# power-v3v8.net
KiCad netlist of a schematic drawn in Altium Designer
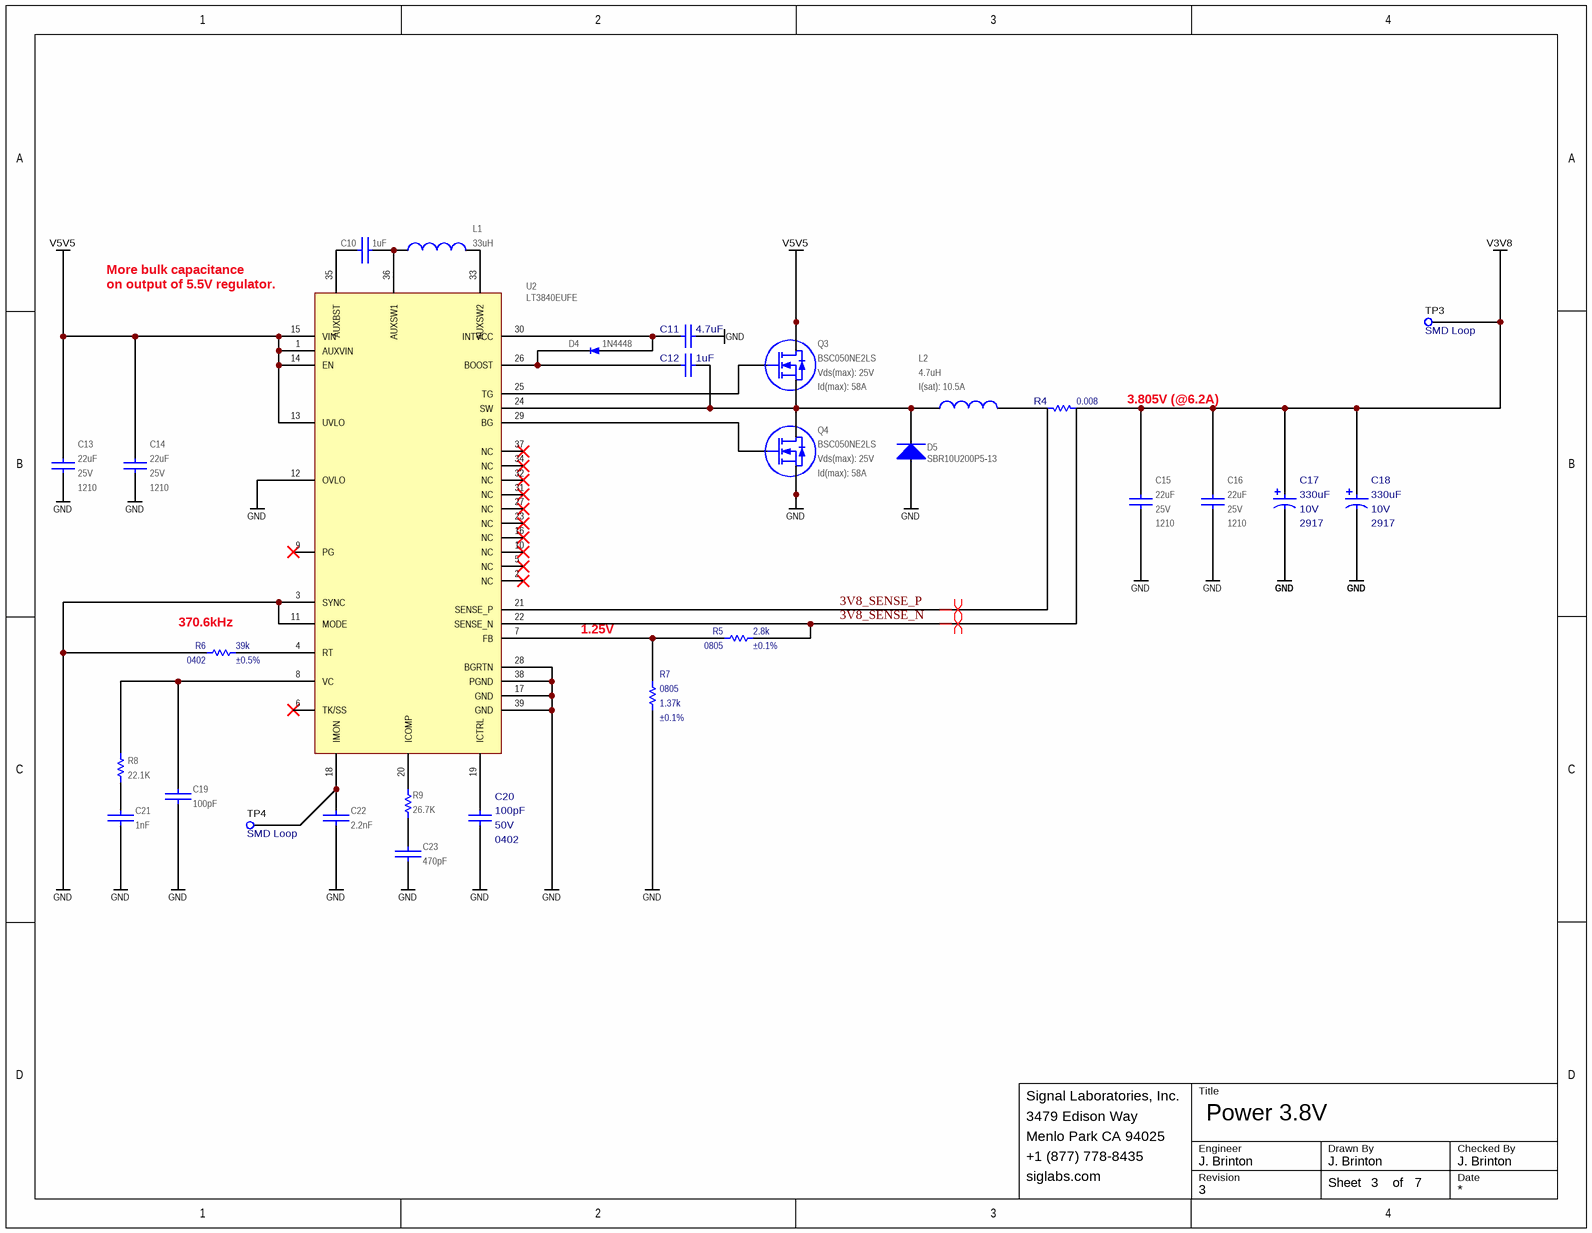
[diagram p0: power-v3v8.SchDoc]

(export (version "E")
  (design (tool "Eeschema 10.0.6"))
  (components
    (comp (ref "C10")
      (value "1uF")
      (footprint "CAPC100X50X55L25N")
      (description "Ceramic Capacitor 1uF ±10% 10V X5R 0402")
      (fields (field (name "MANUFACTURER") "Murata") (field (name "TOLERANCE") "±10%"))
      (libsource (lib "*") (part "CAP"))
    )
    (comp (ref "C11")
      (value "4.7uF")
      (footprint "CAPC160X80X90L20NA")
      (description "Ceramic Capacitor 4.7uF ±10% 25V X5R 0603")
      (fields (field (name "MANUFACTURER") "Samsung") (field (name "TOLERANCE") "±10%"))
      (libsource (lib "capacitors") (part "CAP"))
    )
    (comp (ref "C12")
      (value "1uF")
      (footprint "CAPC100X50X55L25N")
      (description "Ceramic Capacitor 1uF ±10% 10V X5R 0402")
      (fields (field (name "MANUFACTURER") "Murata") (field (name "TOLERANCE") "±10%"))
      (libsource (lib "capacitors") (part "CAP"))
    )
    (comp (ref "C13")
      (value "22uF")
      (footprint "CAPC320X250X270L50N")
      (description "Ceramic Capacitor 22uF ±10% 25V X7R 1210")
      (fields
        (field (name "MANUFACTURER") "Murata")
        (field (name "TOLERANCE") "±10%")
        (field (name "VOLTAGE") "25V")
        (field (name "PACKAGE") "1210")
      )
      (libsource (lib "generic") (part "CAP"))
    )
    (comp (ref "C14")
      (value "22uF")
      (footprint "CAPC320X250X270L50N")
      (description "Ceramic Capacitor 22uF ±10% 25V X7R 1210")
      (fields
        (field (name "MANUFACTURER") "Murata")
        (field (name "TOLERANCE") "±10%")
        (field (name "VOLTAGE") "25V")
        (field (name "PACKAGE") "1210")
      )
      (libsource (lib "generic") (part "CAP"))
    )
    (comp (ref "C15")
      (value "22uF")
      (footprint "CAPC320X250X270L50N")
      (description "Ceramic Capacitor 22uF ±10% 25V X7R 1210")
      (fields
        (field (name "MANUFACTURER") "Murata")
        (field (name "TOLERANCE") "±10%")
        (field (name "VOLTAGE") "25V")
        (field (name "PACKAGE") "1210")
      )
      (libsource (lib "generic") (part "CAP"))
    )
    (comp (ref "C16")
      (value "22uF")
      (footprint "CAPC320X250X270L50N")
      (description "Ceramic Capacitor 22uF ±10% 25V X7R 1210")
      (fields
        (field (name "MANUFACTURER") "Murata")
        (field (name "TOLERANCE") "±10%")
        (field (name "VOLTAGE") "25V")
        (field (name "PACKAGE") "1210")
      )
      (libsource (lib "generic") (part "CAP"))
    )
    (comp (ref "C17")
      (value "330uF")
      (footprint "CAPPM730X435X310L135X240N")
      (description "Tantalum Capacitor 330uF ±10% 10V 2917")
      (fields
        (field (name "MANUFACTURER") "AVX")
        (field (name "TOLERANCE") "±10%")
        (field (name "PACKAGE") "2917")
        (field (name "VOLTAGE") "10V")
      )
      (libsource (lib "avx") (part "CAP_POL"))
    )
    (comp (ref "C18")
      (value "330uF")
      (footprint "CAPPM730X435X310L135X240N")
      (description "Tantalum Capacitor 330uF ±10% 10V 2917")
      (fields
        (field (name "MANUFACTURER") "AVX")
        (field (name "TOLERANCE") "±10%")
        (field (name "PACKAGE") "2917")
        (field (name "VOLTAGE") "10V")
      )
      (libsource (lib "avx") (part "CAP_POL"))
    )
    (comp (ref "C19")
      (value "100pF")
      (footprint "CAPC100X50X55L25N")
      (description "Ceramic Capacitor 100pF ±1% 50V NP0 0402")
      (fields (field (name "MANUFACTURER") "Murata") (field (name "VOLTAGE") "50V"))
      (libsource (lib "*") (part "CAP"))
    )
    (comp (ref "C20")
      (value "100pF")
      (footprint "generic:CAPC100X50X55L25N")
      (description "Ceramic Capacitor 100pF ±10% 50V C0G 0402")
      (fields
        (field (name "MANUFACTURER") "Vishay")
        (field (name "TOLERANCE") "±10%")
        (field (name "PACKAGE") "0402")
        (field (name "VOLTAGE") "50V")
      )
      (libsource (lib "capacitors") (part "CAP"))
    )
    (comp (ref "C21")
      (value "1nF")
      (footprint "CAPC100X50X55L25N")
      (description "Ceramic Capacitor 1nF ±5% 50V NP0 0402")
      (fields (field (name "MANUFACTURER") "Murata") (field (name "VOLTAGE") "50V"))
      (libsource (lib "*") (part "CAP"))
    )
    (comp (ref "C22")
      (value "2.2nF")
      (footprint "CAPC100X50X55L25N")
      (description "Ceramic Capacitor 2.2nF ±5% 25V NP0 0402")
      (fields (field (name "MANUFACTURER") "Kemet") (field (name "TOLERANCE") "±5%"))
      (libsource (lib "*") (part "CAP"))
    )
    (comp (ref "C23")
      (value "470pF")
      (footprint "CAPC100X50X55L25N")
      (description "Ceramic Capacitor 470pF ±5% 50V X7R 0402")
      (fields (field (name "MANUFACTURER") "Murata") (field (name "VOLTAGE") "50V"))
      (libsource (lib "*") (part "CAP"))
    )
    (comp (ref "D4")
      (value "1N4448HWS-7-F")
      (footprint "diodes_inc:SOD323")
      (description "Schottky Diode 80V 250mA SOD323")
      (fields (field (name "MANUFACTURER") "Diodes Inc") (field (name "ALTERNATIVE P/N") "1N4448"))
      (libsource (lib "diodes_inc") (part "1N4448HWS-7-F"))
    )
    (comp (ref "D5")
      (value "SBR10U200P5-13")
      (footprint "DIODES_POWERDI5")
      (description "Schottky Diode 200V 10A SMD")
      (fields (field (name "MANUFACTURER") "Diodes Inc"))
      (libsource (lib "diodes_inc") (part "PDS5100H"))
    )
    (comp (ref "L1")
      (value "33uH")
      (footprint "coilcraft:ME3220")
      (description "Inductor 33uH ±10% 500mA SMD")
      (fields (field (name "MANUFACTURER") "Coilcraft") (field (name "TOLERANCE") "±10%"))
      (libsource (lib "CamBoard_Pico_70.19K") (part "COIL"))
    )
    (comp (ref "L2")
      (value "4.7uH")
      (footprint "coilcraft:XAL6060")
      (description "Inductor 4.7uH,10.5A(sat), SMD")
      (fields
        (field (name "MANUFACTURER") "Coilcraft")
        (field (name "I(SAT)") "10.5A")
        (field (name "Comment") "XAL6060-472ME")
      )
      (libsource (lib "CamBoard_Pico_70.19K") (part "COIL"))
    )
    (comp (ref "Q3")
      (value "BSC050NE2LS")
      (footprint "TDSON-8")
      (description "MOSFET N-Channel Enhancement Mode")
      (fields
        (field (name "MANUFACTURER") "Infineon")
        (field (name "VDS(MAX)") "25V")
        (field (name "ID(MAX)") "58A")
      )
      (libsource (lib "infinion") (part "BSC190N15NS3"))
    )
    (comp (ref "Q4")
      (value "BSC050NE2LS")
      (footprint "TDSON-8")
      (description "MOSFET N-Channel Enhancement Mode")
      (fields
        (field (name "MANUFACTURER") "Infineon")
        (field (name "VDS(MAX)") "25V")
        (field (name "ID(MAX)") "58A")
      )
      (libsource (lib "infinion") (part "BSC190N15NS3"))
    )
    (comp (ref "R4")
      (value "0.008")
      (footprint "susumu:KRL3216T4")
      (description "Current Sense Resistor 8 mOhms +/-1% SMD 4-Terminal")
      (fields (field (name "TOLERANCE") "±1%") (field (name "MANUFACTURER") "Susumu"))
      (libsource (lib "susumu") (part "KRL3216T4A-M-R009-F"))
    )
    (comp (ref "R5")
      (value "2.8k")
      (footprint "RESC2012X70N")
      (description "Thin Film Resistor 2.8k +/-0.1% SMD 0805")
      (fields
        (field (name "TOLERANCE") "±0.1%")
        (field (name "MANUFACTURER") "Yageo")
        (field (name "PACKAGE") "0805")
        (field (name "Comment") "RT0805BRD072K8L")
      )
      (libsource (lib "generic") (part "RES"))
    )
    (comp (ref "R6")
      (value "39k")
      (footprint "RESC1005X40N")
      (description "Thin Film Resistor 39k +/-0.5% SMD 0402")
      (fields
        (field (name "TOLERANCE") "±0.5%")
        (field (name "MANUFACTURER") "Susumu")
        (field (name "PACKAGE") "0402")
        (field (name "Comment") "RR0510P-393-D")
      )
      (libsource (lib "generic") (part "RES"))
    )
    (comp (ref "R7")
      (value "1.37k")
      (footprint "RESC2012X70N")
      (description "Thin Film Resistor 1.37k +/-0.1% SMD 0805")
      (fields
        (field (name "TOLERANCE") "±0.1%")
        (field (name "MANUFACTURER") "Yageo")
        (field (name "PACKAGE") "0805")
        (field (name "Comment") "RT0805BRD071K37L")
      )
      (libsource (lib "generic") (part "RES"))
    )
    (comp (ref "R8")
      (value "22.1K")
      (footprint "generic:RESC1005X40N")
      (description "Thick Film Resistor 22.1k ±1% 0402")
      (fields (field (name "MANUFACTURER") "Panasonic") (field (name "TOLERANCE") "±1%"))
      (libsource (lib "Graviton") (part "RES 0402"))
    )
    (comp (ref "R9")
      (value "26.7K")
      (footprint "generic:RESC1005X40N")
      (description "Thick Film Resistor 26.7k ±1% 0402")
      (fields (field (name "MANUFACTURER") "Panasonic") (field (name "TOLERANCE") "±1%"))
      (libsource (lib "Graviton") (part "RES 0402"))
    )
    (comp (ref "TP3")
      (value "5015")
      (footprint "keystone:5015")
      (description "Test Point SMD")
      (fields (field (name "MANUFACTURER") "Keystone") (field (name "NOTES") "SMD Loop"))
      (libsource (lib "generic") (part "TEST_POINT_SMD_50"))
    )
    (comp (ref "TP4")
      (value "5015")
      (footprint "keystone:5015")
      (description "Test Point SMD")
      (fields (field (name "MANUFACTURER") "Keystone") (field (name "NOTES") "SMD Loop"))
      (libsource (lib "generic") (part "TEST_POINT_SMD_50"))
    )
    (comp (ref "U2")
      (value "LT3840EUFE")
      (footprint "linear:QFN39P40_600X400X80L40X20T465X265N")
      (description "Synchronous Regulator Controller")
      (fields (field (name "MANUFACTURER") "Linear Technology"))
      (libsource (lib "linear") (part "LT3840EUFE"))
    )
  )
  (nets
    (net (code "1") (name "/3V8_SENSE_N") (class "Default")
      (node (ref "R4") (pin "4") (pinfunction "4_4") (pintype "passive"))
      (node (ref "R5") (pin "1") (pinfunction "1_1") (pintype "passive"))
      (node (ref "U2") (pin "22") (pinfunction "SENSE_N_22") (pintype "passive"))
    )
    (net (code "2") (name "/3V8_SENSE_P") (class "Default")
      (node (ref "R4") (pin "3") (pinfunction "3_3") (pintype "passive"))
      (node (ref "U2") (pin "21") (pinfunction "SENSE_P_21") (pintype "passive"))
    )
    (net (code "3") (name "GND") (class "Default")
      (node (ref "C11") (pin "2") (pinfunction "2_2") (pintype "passive"))
      (node (ref "C13") (pin "1") (pinfunction "1_1") (pintype "passive"))
      (node (ref "C14") (pin "1") (pinfunction "1_1") (pintype "passive"))
      (node (ref "C15") (pin "1") (pinfunction "1_1") (pintype "passive"))
      (node (ref "C16") (pin "1") (pinfunction "1_1") (pintype "passive"))
      (node (ref "C17") (pin "2") (pinfunction "2_2") (pintype "passive"))
      (node (ref "C18") (pin "2") (pinfunction "2_2") (pintype "passive"))
      (node (ref "C19") (pin "1") (pinfunction "1_1") (pintype "passive"))
      (node (ref "C20") (pin "2") (pinfunction "2_2") (pintype "passive"))
      (node (ref "C21") (pin "2") (pinfunction "2_2") (pintype "passive"))
      (node (ref "C22") (pin "2") (pinfunction "2_2") (pintype "passive"))
      (node (ref "C23") (pin "1") (pinfunction "1_1") (pintype "passive"))
      (node (ref "D5") (pin "A") (pinfunction "A_A") (pintype "power_in"))
      (node (ref "Q4") (pin "1") (pinfunction "S_1") (pintype "passive"))
      (node (ref "Q4") (pin "2") (pinfunction "S_2") (pintype "passive"))
      (node (ref "Q4") (pin "3") (pinfunction "S_3") (pintype "passive"))
      (node (ref "R6") (pin "2") (pinfunction "2_2") (pintype "passive"))
      (node (ref "R7") (pin "1") (pinfunction "1_1") (pintype "passive"))
      (node (ref "U2") (pin "11") (pinfunction "MODE_11") (pintype "passive"))
      (node (ref "U2") (pin "12") (pinfunction "OVLO_12") (pintype "passive"))
      (node (ref "U2") (pin "17") (pinfunction "GND_17") (pintype "passive"))
      (node (ref "U2") (pin "28") (pinfunction "BGRTN_28") (pintype "passive"))
      (node (ref "U2") (pin "3") (pinfunction "SYNC_3") (pintype "passive"))
      (node (ref "U2") (pin "38") (pinfunction "PGND_38") (pintype "passive"))
      (node (ref "U2") (pin "39") (pinfunction "GND_39") (pintype "passive"))
    )
    (net (code "4") (name "Net-(C21-Pad1)") (class "Default")
      (node (ref "C21") (pin "1") (pinfunction "1_1") (pintype "passive"))
      (node (ref "R8") (pin "1") (pinfunction "1_1") (pintype "passive"))
    )
    (net (code "5") (name "Net-(C23-Pad2)") (class "Default")
      (node (ref "C23") (pin "2") (pinfunction "2_2") (pintype "passive"))
      (node (ref "R9") (pin "2") (pinfunction "2_2") (pintype "passive"))
    )
    (net (code "6") (name "Net-(L2-Pad2)") (class "Default")
      (node (ref "L2") (pin "2") (pinfunction "2_2") (pintype "passive"))
      (node (ref "R4") (pin "1") (pinfunction "1_1") (pintype "passive"))
    )
    (net (code "7") (name "Net-(Q3-G)") (class "Default")
      (node (ref "Q3") (pin "4") (pinfunction "G_4") (pintype "passive"))
      (node (ref "U2") (pin "25") (pinfunction "TG_25") (pintype "passive"))
    )
    (net (code "8") (name "Net-(Q4-G)") (class "Default")
      (node (ref "Q4") (pin "4") (pinfunction "G_4") (pintype "passive"))
      (node (ref "U2") (pin "29") (pinfunction "BG_29") (pintype "passive"))
    )
    (net (code "9") (name "Net-(U2-AUXBST)") (class "Default")
      (node (ref "C10") (pin "2") (pinfunction "2_2") (pintype "passive"))
      (node (ref "U2") (pin "35") (pinfunction "AUXBST_35") (pintype "passive"))
    )
    (net (code "10") (name "Net-(U2-AUXSW1)") (class "Default")
      (node (ref "C10") (pin "1") (pinfunction "1_1") (pintype "passive"))
      (node (ref "L1") (pin "1") (pinfunction "1_1") (pintype "passive"))
      (node (ref "U2") (pin "36") (pinfunction "AUXSW1_36") (pintype "passive"))
    )
    (net (code "11") (name "Net-(U2-AUXSW2)") (class "Default")
      (node (ref "L1") (pin "2") (pinfunction "2_2") (pintype "passive"))
      (node (ref "U2") (pin "33") (pinfunction "AUXSW2_33") (pintype "passive"))
    )
    (net (code "12") (name "Net-(U2-BOOST)") (class "Default")
      (node (ref "C12") (pin "1") (pinfunction "1_1") (pintype "passive"))
      (node (ref "D4") (pin "K") (pinfunction "K_K") (pintype "passive"))
      (node (ref "U2") (pin "26") (pinfunction "BOOST_26") (pintype "passive"))
    )
    (net (code "13") (name "Net-(U2-FB)") (class "Default")
      (node (ref "R5") (pin "2") (pinfunction "2_2") (pintype "passive"))
      (node (ref "R7") (pin "2") (pinfunction "2_2") (pintype "passive"))
      (node (ref "U2") (pin "7") (pinfunction "FB_7") (pintype "passive"))
    )
    (net (code "14") (name "Net-(U2-ICOMP)") (class "Default")
      (node (ref "R9") (pin "1") (pinfunction "1_1") (pintype "passive"))
      (node (ref "U2") (pin "20") (pinfunction "ICOMP_20") (pintype "passive"))
    )
    (net (code "15") (name "Net-(U2-ICTRL)") (class "Default")
      (node (ref "C20") (pin "1") (pinfunction "1_1") (pintype "passive"))
      (node (ref "U2") (pin "19") (pinfunction "ICTRL_19") (pintype "passive"))
    )
    (net (code "16") (name "Net-(U2-IMON)") (class "Default")
      (node (ref "C22") (pin "1") (pinfunction "1_1") (pintype "passive"))
      (node (ref "TP4") (pin "1") (pinfunction "1_1") (pintype "passive"))
      (node (ref "U2") (pin "18") (pinfunction "IMON_18") (pintype "passive"))
    )
    (net (code "17") (name "Net-(U2-INTVCC)") (class "Default")
      (node (ref "C11") (pin "1") (pinfunction "1_1") (pintype "passive"))
      (node (ref "D4") (pin "A") (pinfunction "A_A") (pintype "passive"))
      (node (ref "U2") (pin "30") (pinfunction "INTVCC_30") (pintype "passive"))
    )
    (net (code "18") (name "Net-(U2-RT)") (class "Default")
      (node (ref "R6") (pin "1") (pinfunction "1_1") (pintype "passive"))
      (node (ref "U2") (pin "4") (pinfunction "RT_4") (pintype "passive"))
    )
    (net (code "19") (name "Net-(U2-SW)") (class "Default")
      (node (ref "C12") (pin "2") (pinfunction "2_2") (pintype "passive"))
      (node (ref "D5") (pin "K") (pinfunction "K_K") (pintype "passive"))
      (node (ref "L2") (pin "1") (pinfunction "1_1") (pintype "passive"))
      (node (ref "Q3") (pin "1") (pinfunction "S_1") (pintype "passive"))
      (node (ref "Q3") (pin "2") (pinfunction "S_2") (pintype "passive"))
      (node (ref "Q3") (pin "3") (pinfunction "S_3") (pintype "passive"))
      (node (ref "Q4") (pin "5") (pinfunction "D_5") (pintype "passive"))
      (node (ref "Q4") (pin "6") (pinfunction "D_6") (pintype "passive"))
      (node (ref "Q4") (pin "7") (pinfunction "D_7") (pintype "passive"))
      (node (ref "Q4") (pin "8") (pinfunction "D_8") (pintype "passive"))
      (node (ref "Q4") (pin "9") (pinfunction "D_9") (pintype "passive"))
      (node (ref "U2") (pin "24") (pinfunction "SW_24") (pintype "passive"))
    )
    (net (code "20") (name "Net-(U2-VC)") (class "Default")
      (node (ref "C19") (pin "2") (pinfunction "2_2") (pintype "passive"))
      (node (ref "R8") (pin "2") (pinfunction "2_2") (pintype "passive"))
      (node (ref "U2") (pin "8") (pinfunction "VC_8") (pintype "passive"))
    )
    (net (code "21") (name "V3V8") (class "Default")
      (node (ref "C15") (pin "2") (pinfunction "2_2") (pintype "passive"))
      (node (ref "C16") (pin "2") (pinfunction "2_2") (pintype "passive"))
      (node (ref "C17") (pin "1") (pinfunction "1_1") (pintype "passive"))
      (node (ref "C18") (pin "1") (pinfunction "1_1") (pintype "passive"))
      (node (ref "R4") (pin "2") (pinfunction "2_2") (pintype "passive"))
      (node (ref "TP3") (pin "1") (pinfunction "1_1") (pintype "passive"))
    )
    (net (code "22") (name "V5V5") (class "Default")
      (node (ref "C13") (pin "2") (pinfunction "2_2") (pintype "passive"))
      (node (ref "C14") (pin "2") (pinfunction "2_2") (pintype "passive"))
      (node (ref "Q3") (pin "5") (pinfunction "D_5") (pintype "passive"))
      (node (ref "Q3") (pin "6") (pinfunction "D_6") (pintype "passive"))
      (node (ref "Q3") (pin "7") (pinfunction "D_7") (pintype "passive"))
      (node (ref "Q3") (pin "8") (pinfunction "D_8") (pintype "passive"))
      (node (ref "Q3") (pin "9") (pinfunction "D_9") (pintype "passive"))
      (node (ref "U2") (pin "1") (pinfunction "AUXVIN_1") (pintype "passive"))
      (node (ref "U2") (pin "13") (pinfunction "UVLO_13") (pintype "passive"))
      (node (ref "U2") (pin "14") (pinfunction "EN_14") (pintype "passive"))
      (node (ref "U2") (pin "15") (pinfunction "VIN_15") (pintype "passive"))
    )
    (net (code "23") (name "unconnected-(U2-NC-Pad2)") (class "Default")
      (node (ref "U2") (pin "2") (pinfunction "NC_2") (pintype "passive+no_connect"))
    )
    (net (code "24") (name "unconnected-(U2-NC-Pad5)") (class "Default")
      (node (ref "U2") (pin "5") (pinfunction "NC_5") (pintype "passive+no_connect"))
    )
    (net (code "25") (name "unconnected-(U2-NC-Pad10)") (class "Default")
      (node (ref "U2") (pin "10") (pinfunction "NC_10") (pintype "passive+no_connect"))
    )
    (net (code "26") (name "unconnected-(U2-NC-Pad16)") (class "Default")
      (node (ref "U2") (pin "16") (pinfunction "NC_16") (pintype "passive+no_connect"))
    )
    (net (code "27") (name "unconnected-(U2-NC-Pad23)") (class "Default")
      (node (ref "U2") (pin "23") (pinfunction "NC_23") (pintype "passive+no_connect"))
    )
    (net (code "28") (name "unconnected-(U2-NC-Pad27)") (class "Default")
      (node (ref "U2") (pin "27") (pinfunction "NC_27") (pintype "passive+no_connect"))
    )
    (net (code "29") (name "unconnected-(U2-NC-Pad31)") (class "Default")
      (node (ref "U2") (pin "31") (pinfunction "NC_31") (pintype "passive+no_connect"))
    )
    (net (code "30") (name "unconnected-(U2-NC-Pad32)") (class "Default")
      (node (ref "U2") (pin "32") (pinfunction "NC_32") (pintype "passive+no_connect"))
    )
    (net (code "31") (name "unconnected-(U2-NC-Pad34)") (class "Default")
      (node (ref "U2") (pin "34") (pinfunction "NC_34") (pintype "passive+no_connect"))
    )
    (net (code "32") (name "unconnected-(U2-NC-Pad37)") (class "Default")
      (node (ref "U2") (pin "37") (pinfunction "NC_37") (pintype "passive+no_connect"))
    )
    (net (code "33") (name "unconnected-(U2-PG-Pad9)") (class "Default")
      (node (ref "U2") (pin "9") (pinfunction "PG_9") (pintype "passive+no_connect"))
    )
    (net (code "34") (name "unconnected-(U2-TK{slash}SS-Pad6)") (class "Default")
      (node (ref "U2") (pin "6") (pinfunction "TK/SS_6") (pintype "passive+no_connect"))
    )
  )
)
